# Sheet1.net
KiCad netlist of a schematic drawn in Altium Designer
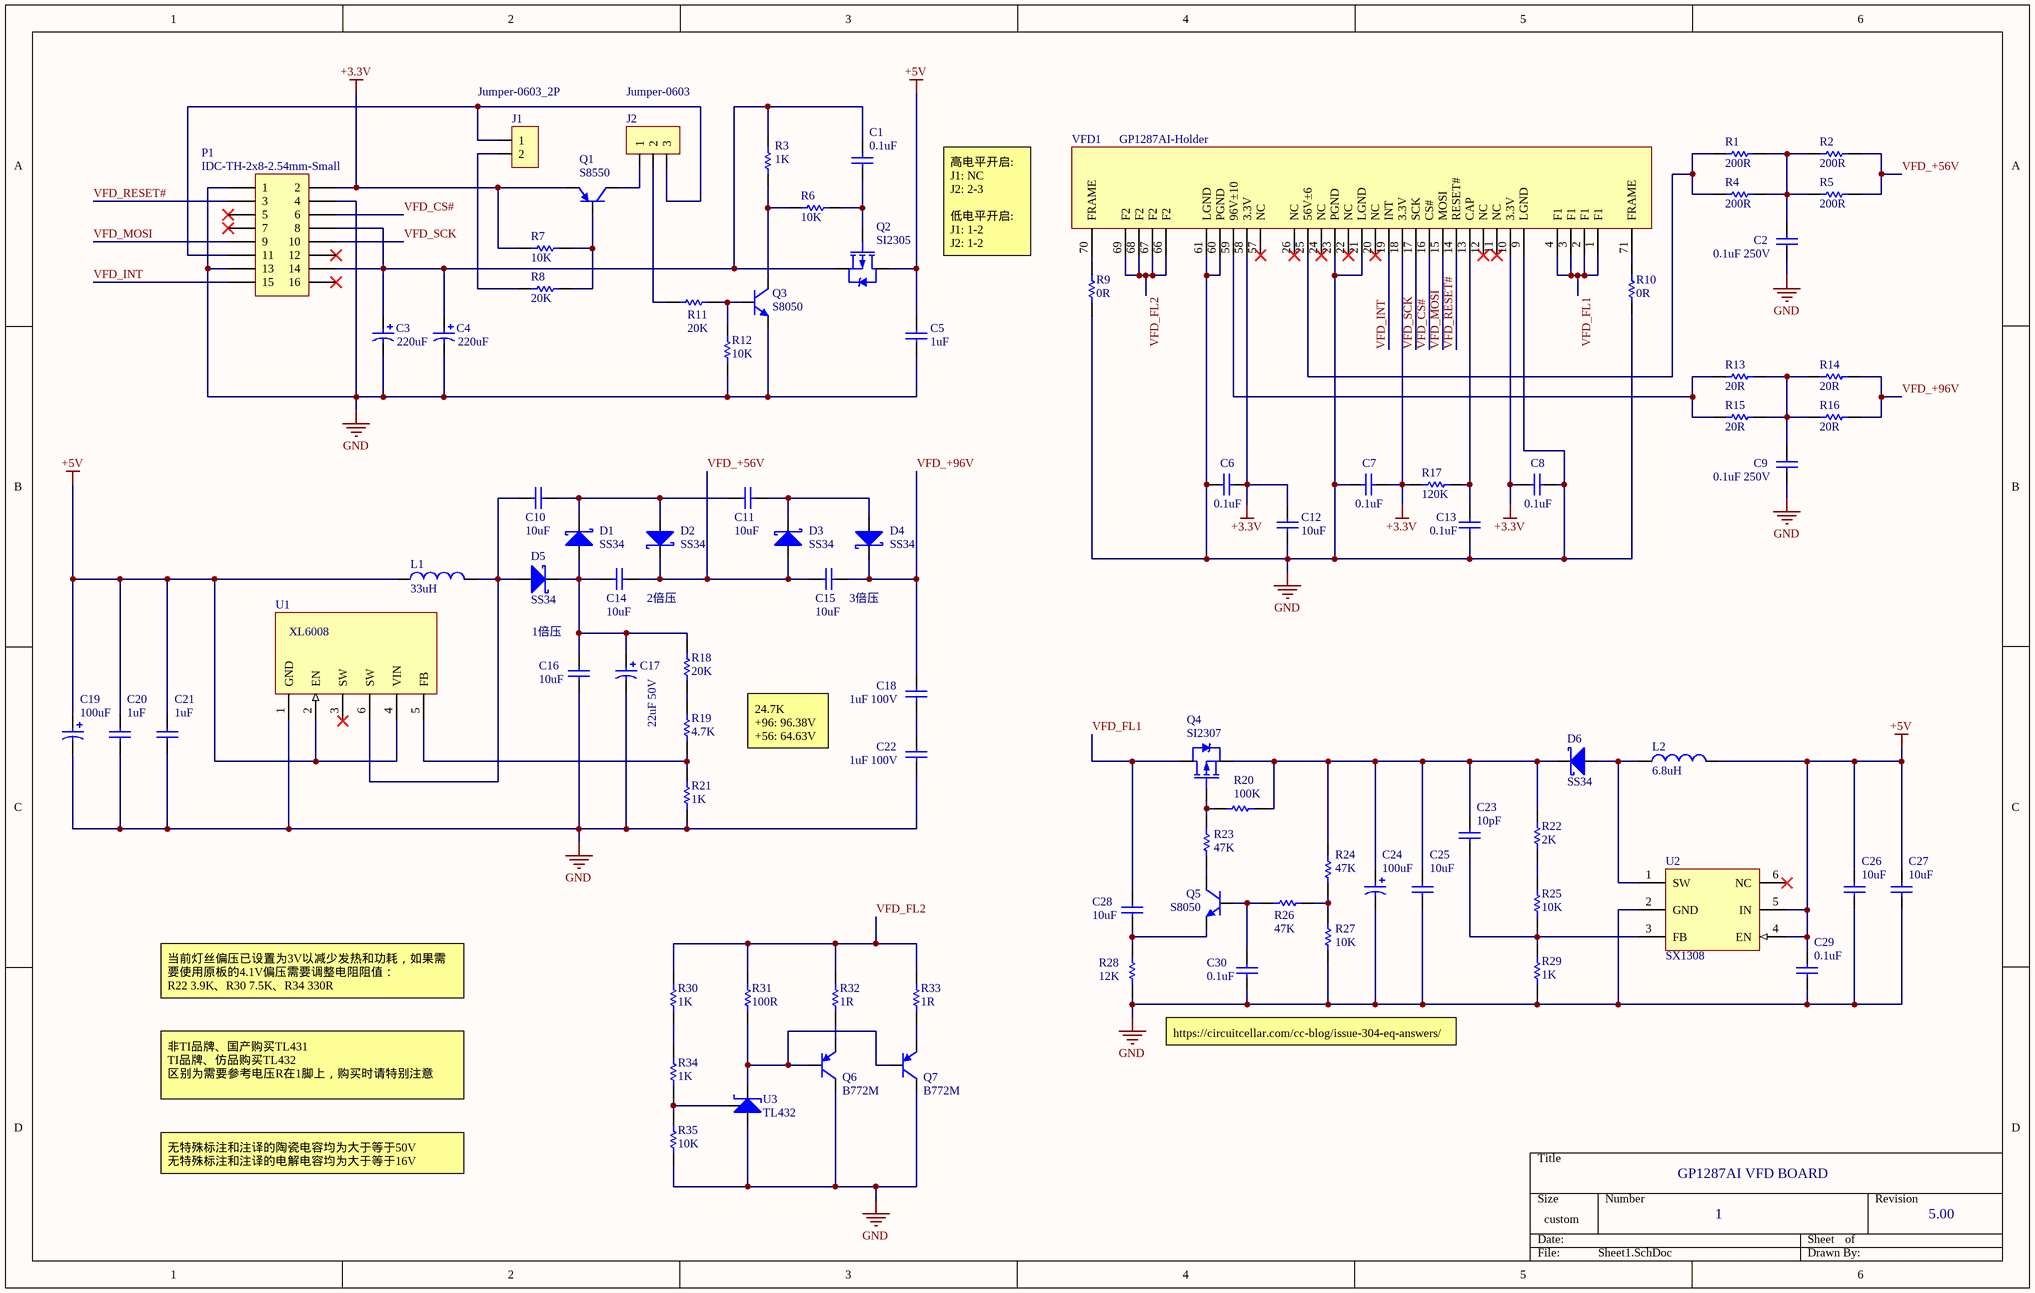
[diagram p0: Sheet1.SchDoc]

(export (version "E")
  (design (tool "Eeschema 10.0.6"))
  (components
    (comp (ref "C1")
      (value "0.1uF")
      (footprint "0603-CAP")
      (libsource (lib "izilzty_Library_Passive") (part "CAP-0603"))
    )
    (comp (ref "C2")
      (value "0.1uF 250V")
      (footprint "1206-CAP")
      (libsource (lib "izilzty_Library_Passive") (part "CAP-1206"))
    )
    (comp (ref "C3")
      (value "220uF")
      (footprint "6.3*7.7-SMD-CAP")
      (libsource (lib "izilzty_Library_Passive") (part "CAP-E-SMD-6.3*7.7"))
    )
    (comp (ref "C4")
      (value "220uF")
      (footprint "6.3*7.7-SMD-CAP")
      (libsource (lib "izilzty_Library_Passive") (part "CAP-E-SMD-6.3*7.7"))
    )
    (comp (ref "C5")
      (value "1uF")
      (footprint "1206-CAP")
      (libsource (lib "izilzty_Library_Passive") (part "CAP-1206"))
    )
    (comp (ref "C6")
      (value "0.1uF")
      (footprint "0603-CAP")
      (libsource (lib "izilzty_Library_Passive") (part "CAP-0603"))
    )
    (comp (ref "C7")
      (value "0.1uF")
      (footprint "0603-CAP")
      (libsource (lib "izilzty_Library_Passive") (part "CAP-0603"))
    )
    (comp (ref "C8")
      (value "0.1uF")
      (footprint "0603-CAP")
      (libsource (lib "izilzty_Library_Passive") (part "CAP-0603"))
    )
    (comp (ref "C9")
      (value "0.1uF 250V")
      (footprint "1206-CAP")
      (libsource (lib "izilzty_Library_Passive") (part "CAP-1206"))
    )
    (comp (ref "C10")
      (value "10uF")
      (footprint "1206-CAP")
      (libsource (lib "izilzty_Library_Passive") (part "CAP-1206"))
    )
    (comp (ref "C11")
      (value "10uF")
      (footprint "1206-CAP")
      (libsource (lib "izilzty_Library_Passive") (part "CAP-1206"))
    )
    (comp (ref "C12")
      (value "10uF")
      (footprint "1206-CAP")
      (libsource (lib "izilzty_Library_Passive") (part "CAP-1206"))
    )
    (comp (ref "C13")
      (value "0.1uF")
      (footprint "0603-CAP")
      (libsource (lib "izilzty_Library_Passive") (part "CAP-0603"))
    )
    (comp (ref "C14")
      (value "10uF")
      (footprint "1206-CAP")
      (libsource (lib "izilzty_Library_Passive") (part "CAP-1206"))
    )
    (comp (ref "C15")
      (value "10uF")
      (footprint "1206-CAP")
      (libsource (lib "izilzty_Library_Passive") (part "CAP-1206"))
    )
    (comp (ref "C16")
      (value "10uF")
      (footprint "1206-CAP")
      (libsource (lib "izilzty_Library_Passive") (part "CAP-1206"))
    )
    (comp (ref "C17")
      (value "22uF 50V")
      (footprint "6.3*5.4-SMD-CAP")
      (libsource (lib "izilzty_Library_Passive") (part "CAP-E-SMD-6.3*5.4"))
    )
    (comp (ref "C18")
      (value "1uF 100V")
      (footprint "1206-CAP")
      (libsource (lib "izilzty_Library_Passive") (part "CAP-1206"))
    )
    (comp (ref "C19")
      (value "100uF")
      (footprint "6.3*5.4-SMD-CAP")
      (libsource (lib "izilzty_Library_Passive") (part "CAP-E-SMD-6.3*5.4"))
    )
    (comp (ref "C20")
      (value "1uF")
      (footprint "0603-CAP")
      (libsource (lib "izilzty_Library_Passive") (part "CAP-0603"))
    )
    (comp (ref "C21")
      (value "1uF")
      (footprint "0603-CAP")
      (libsource (lib "izilzty_Library_Passive") (part "CAP-0603"))
    )
    (comp (ref "C22")
      (value "1uF 100V")
      (footprint "1206-CAP")
      (libsource (lib "izilzty_Library_Passive") (part "CAP-1206"))
    )
    (comp (ref "C23")
      (value "10pF")
      (footprint "0603-CAP")
      (libsource (lib "izilzty_Library_Passive") (part "CAP-0603"))
    )
    (comp (ref "C24")
      (value "100uF")
      (footprint "6.3*5.4-SMD-CAP")
      (libsource (lib "izilzty_Library_Passive") (part "CAP-E-SMD-6.3*5.4"))
    )
    (comp (ref "C25")
      (value "10uF")
      (footprint "1206-CAP")
      (libsource (lib "izilzty_Library_Passive") (part "CAP-1206"))
    )
    (comp (ref "C26")
      (value "10uF")
      (footprint "1206-CAP")
      (libsource (lib "izilzty_Library_Passive") (part "CAP-1206"))
    )
    (comp (ref "C27")
      (value "10uF")
      (footprint "1206-CAP")
      (libsource (lib "izilzty_Library_Passive") (part "CAP-1206"))
    )
    (comp (ref "C28")
      (value "10uF")
      (footprint "1206-CAP")
      (libsource (lib "izilzty_Library_Passive") (part "CAP-1206"))
    )
    (comp (ref "C29")
      (value "0.1uF")
      (footprint "0603-CAP")
      (libsource (lib "izilzty_Library_Passive") (part "CAP-0603"))
    )
    (comp (ref "C30")
      (value "0.1uF")
      (footprint "0603-CAP")
      (libsource (lib "izilzty_Library_Passive") (part "CAP-0603"))
    )
    (comp (ref "D1")
      (value "SS34")
      (footprint "DO-214AC-DIODE-SC_M")
      (libsource (lib "izilzty_Library_Passive") (part "Diode-Schottky-DO214AC"))
    )
    (comp (ref "D2")
      (value "SS34")
      (footprint "DO-214AC-DIODE-SC_M")
      (libsource (lib "izilzty_Library_Passive") (part "Diode-Schottky-DO214AC"))
    )
    (comp (ref "D3")
      (value "SS34")
      (footprint "DO-214AC-DIODE-SC_M")
      (libsource (lib "izilzty_Library_Passive") (part "Diode-Schottky-DO214AC"))
    )
    (comp (ref "D4")
      (value "SS34")
      (footprint "DO-214AC-DIODE-SC_M")
      (libsource (lib "izilzty_Library_Passive") (part "Diode-Schottky-DO214AC"))
    )
    (comp (ref "D5")
      (value "SS34")
      (footprint "DO-214AC-DIODE-SC_M")
      (libsource (lib "izilzty_Library_Passive") (part "Diode-Schottky-DO214AC"))
    )
    (comp (ref "D6")
      (value "SS34")
      (footprint "DO-214AC-DIODE-SC_M")
      (libsource (lib "izilzty_Library_Passive") (part "Diode-Schottky-DO214AC"))
    )
    (comp (ref "J1")
      (value "Jumper-0603_2P")
      (footprint "0603-JUMPER_2P")
      (libsource (lib "izilzty_Library_Passive") (part "Jumper-0603_2P"))
    )
    (comp (ref "J2")
      (value "Jumper-0603")
      (footprint "0603-JUMPER")
      (libsource (lib "izilzty_Library_Passive") (part "Jumper-0603"))
    )
    (comp (ref "L1")
      (value "33uH")
      (footprint "SMD0650_M")
      (libsource (lib "izilzty_Library_Passive") (part "Inductor-SMD0650"))
    )
    (comp (ref "L2")
      (value "6.8uH")
      (footprint "SMD0650_M")
      (libsource (lib "izilzty_Library_Passive") (part "Inductor-SMD0650"))
    )
    (comp (ref "P1")
      (value "IDC-TH-2x8-2.54mm-Small")
      (footprint "IDC_TH_L_SMALL_16P")
      (libsource (lib "izilzty_Library_Connector") (part "IDC-TH-2x8-2.54mm-Small"))
    )
    (comp (ref "Q1")
      (value "S8550")
      (footprint "SOT-23-3_M")
      (libsource (lib "izilzty_Library_Passive") (part "PNP-SOT23-3"))
    )
    (comp (ref "Q2")
      (value "SI2305")
      (footprint "SOT-23-3_M")
      (libsource (lib "izilzty_Library_Passive") (part "PMOS-SOT23-3"))
    )
    (comp (ref "Q3")
      (value "S8050")
      (footprint "SOT-23-3_M")
      (libsource (lib "izilzty_Library_Passive") (part "NPN-SOT23-3"))
    )
    (comp (ref "Q4")
      (value "SI2307")
      (footprint "SOT-23-3_M")
      (libsource (lib "izilzty_Library_Passive") (part "PMOS-SOT23-3"))
    )
    (comp (ref "Q5")
      (value "S8050")
      (footprint "SOT-23-3_M")
      (libsource (lib "izilzty_Library_Passive") (part "NPN-SOT23-3"))
    )
    (comp (ref "Q6")
      (value "B772M")
      (footprint "TO252-2L_M")
      (libsource (lib "izilzty_Library_Passive") (part "PNP-TO252-2L"))
    )
    (comp (ref "Q7")
      (value "B772M")
      (footprint "TO252-2L_M")
      (libsource (lib "izilzty_Library_Passive") (part "PNP-TO252-2L"))
    )
    (comp (ref "R1")
      (value "200R")
      (footprint "1206-RES")
      (libsource (lib "izilzty_Library_Passive") (part "RES-1206"))
    )
    (comp (ref "R2")
      (value "200R")
      (footprint "1206-RES")
      (libsource (lib "izilzty_Library_Passive") (part "RES-1206"))
    )
    (comp (ref "R3")
      (value "1K")
      (footprint "0603-RES")
      (libsource (lib "izilzty_Library_Passive") (part "RES-0603"))
    )
    (comp (ref "R4")
      (value "200R")
      (footprint "1206-RES")
      (libsource (lib "izilzty_Library_Passive") (part "RES-1206"))
    )
    (comp (ref "R5")
      (value "200R")
      (footprint "1206-RES")
      (libsource (lib "izilzty_Library_Passive") (part "RES-1206"))
    )
    (comp (ref "R6")
      (value "10K")
      (footprint "0603-RES")
      (libsource (lib "izilzty_Library_Passive") (part "RES-0603"))
    )
    (comp (ref "R7")
      (value "10K")
      (footprint "0603-RES")
      (libsource (lib "izilzty_Library_Passive") (part "RES-0603"))
    )
    (comp (ref "R8")
      (value "20K")
      (footprint "0603-RES")
      (libsource (lib "izilzty_Library_Passive") (part "RES-0603"))
    )
    (comp (ref "R9")
      (value "0R")
      (footprint "0603-RES")
      (libsource (lib "izilzty_Library_Passive") (part "RES-0603"))
    )
    (comp (ref "R10")
      (value "0R")
      (footprint "0603-RES")
      (libsource (lib "izilzty_Library_Passive") (part "RES-0603"))
    )
    (comp (ref "R11")
      (value "20K")
      (footprint "0603-RES")
      (libsource (lib "izilzty_Library_Passive") (part "RES-0603"))
    )
    (comp (ref "R12")
      (value "10K")
      (footprint "0603-RES")
      (libsource (lib "izilzty_Library_Passive") (part "RES-0603"))
    )
    (comp (ref "R13")
      (value "20R")
      (footprint "1206-RES")
      (libsource (lib "izilzty_Library_Passive") (part "RES-1206"))
    )
    (comp (ref "R14")
      (value "20R")
      (footprint "1206-RES")
      (libsource (lib "izilzty_Library_Passive") (part "RES-1206"))
    )
    (comp (ref "R15")
      (value "20R")
      (footprint "1206-RES")
      (libsource (lib "izilzty_Library_Passive") (part "RES-1206"))
    )
    (comp (ref "R16")
      (value "20R")
      (footprint "1206-RES")
      (libsource (lib "izilzty_Library_Passive") (part "RES-1206"))
    )
    (comp (ref "R17")
      (value "120K")
      (footprint "0603-RES")
      (libsource (lib "izilzty_Library_Passive") (part "RES-0603"))
    )
    (comp (ref "R18")
      (value "20K")
      (footprint "0603-RES")
      (libsource (lib "izilzty_Library_Passive") (part "RES-0603"))
    )
    (comp (ref "R19")
      (value "4.7K")
      (footprint "0603-RES")
      (libsource (lib "izilzty_Library_Passive") (part "RES-0603"))
    )
    (comp (ref "R20")
      (value "100K")
      (footprint "0603-RES")
      (libsource (lib "izilzty_Library_Passive") (part "RES-0603"))
    )
    (comp (ref "R21")
      (value "1K")
      (footprint "0603-RES")
      (libsource (lib "izilzty_Library_Passive") (part "RES-0603"))
    )
    (comp (ref "R22")
      (value "2K")
      (footprint "0603-RES")
      (libsource (lib "izilzty_Library_Passive") (part "RES-0603"))
    )
    (comp (ref "R23")
      (value "47K")
      (footprint "0603-RES")
      (libsource (lib "izilzty_Library_Passive") (part "RES-0603"))
    )
    (comp (ref "R24")
      (value "47K")
      (footprint "0603-RES")
      (libsource (lib "izilzty_Library_Passive") (part "RES-0603"))
    )
    (comp (ref "R25")
      (value "10K")
      (footprint "0603-RES")
      (libsource (lib "izilzty_Library_Passive") (part "RES-0603"))
    )
    (comp (ref "R26")
      (value "47K")
      (footprint "0603-RES")
      (libsource (lib "izilzty_Library_Passive") (part "RES-0603"))
    )
    (comp (ref "R27")
      (value "10K")
      (footprint "0603-RES")
      (libsource (lib "izilzty_Library_Passive") (part "RES-0603"))
    )
    (comp (ref "R28")
      (value "12K")
      (footprint "0603-RES")
      (libsource (lib "izilzty_Library_Passive") (part "RES-0603"))
    )
    (comp (ref "R29")
      (value "1K")
      (footprint "0603-RES")
      (libsource (lib "izilzty_Library_Passive") (part "RES-0603"))
    )
    (comp (ref "R30")
      (value "1K")
      (footprint "0603-RES")
      (libsource (lib "izilzty_Library_Passive") (part "RES-0603"))
    )
    (comp (ref "R31")
      (value "100R")
      (footprint "0603-RES")
      (libsource (lib "izilzty_Library_Passive") (part "RES-0603"))
    )
    (comp (ref "R32")
      (value "1R")
      (footprint "1206-RES")
      (libsource (lib "izilzty_Library_Passive") (part "RES-1206"))
    )
    (comp (ref "R33")
      (value "1R")
      (footprint "1206-RES")
      (libsource (lib "izilzty_Library_Passive") (part "RES-1206"))
    )
    (comp (ref "R34")
      (value "1K")
      (footprint "0603-RES")
      (libsource (lib "izilzty_Library_Passive") (part "RES-0603"))
    )
    (comp (ref "R35")
      (value "10K")
      (footprint "0603-RES")
      (libsource (lib "izilzty_Library_Passive") (part "RES-0603"))
    )
    (comp (ref "U1")
      (value "XL6008")
      (footprint "TO252-5L_M")
      (description "60V 3A  Buck-Boost Converter 400Khz (TO252-5L)")
      (libsource (lib "izilzty_Library_IC") (part "XL6008"))
    )
    (comp (ref "U2")
      (value "SX1308")
      (footprint "SOT-23-6_M")
      (description "26V 2A Boost Converter 1.2MHz (SOT-23-6)")
      (libsource (lib "izilzty_Library_IC") (part "SX1308"))
    )
    (comp (ref "U3")
      (value "TL432")
      (footprint "SOT-23-3_M")
      (description "Precision Programmable Reference")
      (libsource (lib "izilzty_Library_IC") (part "TL432-SOT23-3"))
    )
    (comp (ref "VFD1")
      (value "GP1287AI-Holder")
      (footprint "GP1287AI-HOLDER")
      (description "256*50 Graphic VFD")
      (libsource (lib "izilzty_Library_IC") (part "GP1287AI-Holder"))
    )
  )
  (nets
    (net (code "1") (name "+3.3V") (class "Default")
      (node (ref "C12") (pin "2") (pinfunction "2_2") (pintype "passive"))
      (node (ref "C6") (pin "2") (pinfunction "2_2") (pintype "passive"))
      (node (ref "C7") (pin "2") (pinfunction "2_2") (pintype "passive"))
      (node (ref "C8") (pin "1") (pinfunction "1_1") (pintype "passive"))
      (node (ref "P1") (pin "2") (pinfunction "2_2") (pintype "passive"))
      (node (ref "Q1") (pin "2") (pinfunction "E_2") (pintype "passive"))
      (node (ref "R17") (pin "1") (pinfunction "1_1") (pintype "passive"))
      (node (ref "R7") (pin "1") (pinfunction "1_1") (pintype "passive"))
      (node (ref "VFD1") (pin "10") (pinfunction "3.3V_10") (pintype "passive"))
      (node (ref "VFD1") (pin "18") (pinfunction "3.3V_18") (pintype "passive"))
      (node (ref "VFD1") (pin "58") (pinfunction "3.3V_58") (pintype "passive"))
    )
    (net (code "2") (name "+5V") (class "Default")
      (node (ref "C19") (pin "1") (pinfunction "1_1") (pintype "passive"))
      (node (ref "C20") (pin "2") (pinfunction "2_2") (pintype "passive"))
      (node (ref "C21") (pin "2") (pinfunction "2_2") (pintype "passive"))
      (node (ref "C26") (pin "2") (pinfunction "2_2") (pintype "passive"))
      (node (ref "C27") (pin "2") (pinfunction "2_2") (pintype "passive"))
      (node (ref "C29") (pin "2") (pinfunction "2_2") (pintype "passive"))
      (node (ref "C5") (pin "2") (pinfunction "2_2") (pintype "passive"))
      (node (ref "L1") (pin "1") (pinfunction "1_1") (pintype "passive"))
      (node (ref "L2") (pin "2") (pinfunction "2_2") (pintype "passive"))
      (node (ref "Q2") (pin "3") (pinfunction "D_3") (pintype "passive"))
      (node (ref "U1") (pin "2") (pinfunction "EN_2") (pintype "input"))
      (node (ref "U1") (pin "4") (pinfunction "VIN_4") (pintype "power_in"))
      (node (ref "U2") (pin "4") (pinfunction "EN_4") (pintype "input"))
      (node (ref "U2") (pin "5") (pinfunction "IN_5") (pintype "power_in"))
    )
    (net (code "3") (name "/VFD_+56V") (class "Default")
      (node (ref "C14") (pin "2") (pinfunction "2_2") (pintype "passive"))
      (node (ref "C15") (pin "1") (pinfunction "1_1") (pintype "passive"))
      (node (ref "D2") (pin "1") (pinfunction "K_1") (pintype "passive"))
      (node (ref "D3") (pin "2") (pinfunction "A_2") (pintype "passive"))
      (node (ref "R2") (pin "1") (pinfunction "1_1") (pintype "passive"))
      (node (ref "R5") (pin "1") (pinfunction "1_1") (pintype "passive"))
    )
    (net (code "4") (name "/VFD_+96V") (class "Default")
      (node (ref "C15") (pin "2") (pinfunction "2_2") (pintype "passive"))
      (node (ref "C18") (pin "2") (pinfunction "2_2") (pintype "passive"))
      (node (ref "D4") (pin "1") (pinfunction "K_1") (pintype "passive"))
      (node (ref "R14") (pin "1") (pinfunction "1_1") (pintype "passive"))
      (node (ref "R16") (pin "1") (pinfunction "1_1") (pintype "passive"))
    )
    (net (code "5") (name "/VFD_CS#") (class "Default")
      (node (ref "P1") (pin "6") (pinfunction "6_6") (pintype "passive"))
      (node (ref "VFD1") (pin "16") (pinfunction "CS#_16") (pintype "passive"))
    )
    (net (code "6") (name "/VFD_FL1") (class "Default")
      (node (ref "C28") (pin "2") (pinfunction "2_2") (pintype "passive"))
      (node (ref "Q4") (pin "3") (pinfunction "D_3") (pintype "passive"))
      (node (ref "VFD1") (pin "1") (pinfunction "F1_1") (pintype "power_in"))
      (node (ref "VFD1") (pin "2") (pinfunction "F1_2") (pintype "power_in"))
      (node (ref "VFD1") (pin "3") (pinfunction "F1_3") (pintype "power_in"))
      (node (ref "VFD1") (pin "4") (pinfunction "F1_4") (pintype "power_in"))
    )
    (net (code "7") (name "/VFD_FL2") (class "Default")
      (node (ref "R30") (pin "2") (pinfunction "2_2") (pintype "passive"))
      (node (ref "R31") (pin "2") (pinfunction "2_2") (pintype "passive"))
      (node (ref "R32") (pin "2") (pinfunction "2_2") (pintype "passive"))
      (node (ref "R33") (pin "2") (pinfunction "2_2") (pintype "passive"))
      (node (ref "VFD1") (pin "66") (pinfunction "F2_66") (pintype "passive"))
      (node (ref "VFD1") (pin "67") (pinfunction "F2_67") (pintype "passive"))
      (node (ref "VFD1") (pin "68") (pinfunction "F2_68") (pintype "passive"))
      (node (ref "VFD1") (pin "69") (pinfunction "F2_69") (pintype "passive"))
    )
    (net (code "8") (name "/VFD_INT") (class "Default")
      (node (ref "P1") (pin "15") (pinfunction "15_15") (pintype "passive"))
      (node (ref "VFD1") (pin "19") (pinfunction "INT_19") (pintype "passive"))
    )
    (net (code "9") (name "/VFD_MOSI") (class "Default")
      (node (ref "P1") (pin "9") (pinfunction "9_9") (pintype "passive"))
      (node (ref "VFD1") (pin "15") (pinfunction "MOSI_15") (pintype "passive"))
    )
    (net (code "10") (name "/VFD_RESET#") (class "Default")
      (node (ref "P1") (pin "3") (pinfunction "3_3") (pintype "passive"))
      (node (ref "VFD1") (pin "14") (pinfunction "RESET#_14") (pintype "passive"))
    )
    (net (code "11") (name "/VFD_SCK") (class "Default")
      (node (ref "P1") (pin "10") (pinfunction "10_10") (pintype "passive"))
      (node (ref "VFD1") (pin "17") (pinfunction "SCK_17") (pintype "passive"))
    )
    (net (code "12") (name "GND") (class "Default")
      (node (ref "C12") (pin "1") (pinfunction "1_1") (pintype "passive"))
      (node (ref "C13") (pin "1") (pinfunction "1_1") (pintype "passive"))
      (node (ref "C16") (pin "1") (pinfunction "1_1") (pintype "passive"))
      (node (ref "C17") (pin "2") (pinfunction "2_2") (pintype "passive"))
      (node (ref "C19") (pin "2") (pinfunction "2_2") (pintype "passive"))
      (node (ref "C2") (pin "1") (pinfunction "1_1") (pintype "passive"))
      (node (ref "C20") (pin "1") (pinfunction "1_1") (pintype "passive"))
      (node (ref "C21") (pin "1") (pinfunction "1_1") (pintype "passive"))
      (node (ref "C22") (pin "1") (pinfunction "1_1") (pintype "passive"))
      (node (ref "C24") (pin "2") (pinfunction "2_2") (pintype "passive"))
      (node (ref "C25") (pin "1") (pinfunction "1_1") (pintype "passive"))
      (node (ref "C26") (pin "1") (pinfunction "1_1") (pintype "passive"))
      (node (ref "C27") (pin "1") (pinfunction "1_1") (pintype "passive"))
      (node (ref "C29") (pin "1") (pinfunction "1_1") (pintype "passive"))
      (node (ref "C3") (pin "2") (pinfunction "2_2") (pintype "passive"))
      (node (ref "C30") (pin "1") (pinfunction "1_1") (pintype "passive"))
      (node (ref "C4") (pin "2") (pinfunction "2_2") (pintype "passive"))
      (node (ref "C5") (pin "1") (pinfunction "1_1") (pintype "passive"))
      (node (ref "C6") (pin "1") (pinfunction "1_1") (pintype "passive"))
      (node (ref "C7") (pin "1") (pinfunction "1_1") (pintype "passive"))
      (node (ref "C8") (pin "2") (pinfunction "2_2") (pintype "passive"))
      (node (ref "C9") (pin "1") (pinfunction "1_1") (pintype "passive"))
      (node (ref "P1") (pin "1") (pinfunction "1_1") (pintype "passive"))
      (node (ref "P1") (pin "13") (pinfunction "13_13") (pintype "passive"))
      (node (ref "P1") (pin "4") (pinfunction "4_4") (pintype "passive"))
      (node (ref "Q3") (pin "2") (pinfunction "E_2") (pintype "passive"))
      (node (ref "Q6") (pin "2") (pinfunction "C_2") (pintype "passive"))
      (node (ref "Q7") (pin "2") (pinfunction "C_2") (pintype "passive"))
      (node (ref "R10") (pin "2") (pinfunction "2_2") (pintype "passive"))
      (node (ref "R12") (pin "2") (pinfunction "2_2") (pintype "passive"))
      (node (ref "R21") (pin "2") (pinfunction "2_2") (pintype "passive"))
      (node (ref "R27") (pin "1") (pinfunction "1_1") (pintype "passive"))
      (node (ref "R28") (pin "1") (pinfunction "1_1") (pintype "passive"))
      (node (ref "R29") (pin "1") (pinfunction "1_1") (pintype "passive"))
      (node (ref "R35") (pin "1") (pinfunction "1_1") (pintype "passive"))
      (node (ref "R9") (pin "2") (pinfunction "2_2") (pintype "passive"))
      (node (ref "U1") (pin "1") (pinfunction "GND_1") (pintype "power_in"))
      (node (ref "U2") (pin "2") (pinfunction "GND_2") (pintype "power_in"))
      (node (ref "U3") (pin "3") (pinfunction "A_3") (pintype "passive"))
      (node (ref "VFD1") (pin "21") (pinfunction "LGND_21") (pintype "passive"))
      (node (ref "VFD1") (pin "23") (pinfunction "PGND_23") (pintype "passive"))
      (node (ref "VFD1") (pin "60") (pinfunction "PGND_60") (pintype "passive"))
      (node (ref "VFD1") (pin "61") (pinfunction "LGND_61") (pintype "passive"))
      (node (ref "VFD1") (pin "9") (pinfunction "LGND_9") (pintype "passive"))
    )
    (net (code "13") (name "Net-(C2-Pad2)") (class "Default")
      (node (ref "C2") (pin "2") (pinfunction "2_2") (pintype "passive"))
      (node (ref "R1") (pin "1") (pinfunction "1_1") (pintype "passive"))
      (node (ref "R2") (pin "2") (pinfunction "2_2") (pintype "passive"))
      (node (ref "R4") (pin "1") (pinfunction "1_1") (pintype "passive"))
      (node (ref "R5") (pin "2") (pinfunction "2_2") (pintype "passive"))
    )
    (net (code "14") (name "Net-(C9-Pad2)") (class "Default")
      (node (ref "C9") (pin "2") (pinfunction "2_2") (pintype "passive"))
      (node (ref "R13") (pin "1") (pinfunction "1_1") (pintype "passive"))
      (node (ref "R14") (pin "2") (pinfunction "2_2") (pintype "passive"))
      (node (ref "R15") (pin "1") (pinfunction "1_1") (pintype "passive"))
      (node (ref "R16") (pin "2") (pinfunction "2_2") (pintype "passive"))
    )
    (net (code "15") (name "Net-(C18-Pad1)") (class "Default")
      (node (ref "C18") (pin "1") (pinfunction "1_1") (pintype "passive"))
      (node (ref "C22") (pin "2") (pinfunction "2_2") (pintype "passive"))
    )
    (net (code "16") (name "Net-(D1-A)") (class "Default")
      (node (ref "C14") (pin "1") (pinfunction "1_1") (pintype "passive"))
      (node (ref "C16") (pin "2") (pinfunction "2_2") (pintype "passive"))
      (node (ref "C17") (pin "1") (pinfunction "1_1") (pintype "passive"))
      (node (ref "D1") (pin "2") (pinfunction "A_2") (pintype "passive"))
      (node (ref "D5") (pin "1") (pinfunction "K_1") (pintype "passive"))
      (node (ref "R18") (pin "1") (pinfunction "1_1") (pintype "passive"))
    )
    (net (code "17") (name "Net-(D1-K)") (class "Default")
      (node (ref "C10") (pin "2") (pinfunction "2_2") (pintype "passive"))
      (node (ref "C11") (pin "1") (pinfunction "1_1") (pintype "passive"))
      (node (ref "D1") (pin "1") (pinfunction "K_1") (pintype "passive"))
      (node (ref "D2") (pin "2") (pinfunction "A_2") (pintype "passive"))
    )
    (net (code "18") (name "Net-(D3-K)") (class "Default")
      (node (ref "C11") (pin "2") (pinfunction "2_2") (pintype "passive"))
      (node (ref "D3") (pin "1") (pinfunction "K_1") (pintype "passive"))
      (node (ref "D4") (pin "2") (pinfunction "A_2") (pintype "passive"))
    )
    (net (code "19") (name "Net-(D5-A)") (class "Default")
      (node (ref "C10") (pin "1") (pinfunction "1_1") (pintype "passive"))
      (node (ref "D5") (pin "2") (pinfunction "A_2") (pintype "passive"))
      (node (ref "L1") (pin "2") (pinfunction "2_2") (pintype "passive"))
      (node (ref "U1") (pin "6") (pinfunction "SW_6") (pintype "power_in"))
    )
    (net (code "20") (name "Net-(D6-A)") (class "Default")
      (node (ref "D6") (pin "2") (pinfunction "A_2") (pintype "passive"))
      (node (ref "L2") (pin "1") (pinfunction "1_1") (pintype "passive"))
      (node (ref "U2") (pin "1") (pinfunction "SW_1") (pintype "passive"))
    )
    (net (code "21") (name "Net-(D6-K)") (class "Default")
      (node (ref "C23") (pin "2") (pinfunction "2_2") (pintype "passive"))
      (node (ref "C24") (pin "1") (pinfunction "1_1") (pintype "passive"))
      (node (ref "C25") (pin "2") (pinfunction "2_2") (pintype "passive"))
      (node (ref "D6") (pin "1") (pinfunction "K_1") (pintype "passive"))
      (node (ref "Q4") (pin "2") (pinfunction "S_2") (pintype "passive"))
      (node (ref "R20") (pin "2") (pinfunction "2_2") (pintype "passive"))
      (node (ref "R22") (pin "2") (pinfunction "2_2") (pintype "passive"))
      (node (ref "R24") (pin "2") (pinfunction "2_2") (pintype "passive"))
    )
    (net (code "22") (name "Net-(J1-Pad1)") (class "Default")
      (node (ref "J1") (pin "1") (pinfunction "1_1") (pintype "passive"))
      (node (ref "J2") (pin "3") (pinfunction "3_3") (pintype "passive"))
      (node (ref "P1") (pin "11") (pinfunction "11_11") (pintype "passive"))
    )
    (net (code "23") (name "Net-(J1-Pad2)") (class "Default")
      (node (ref "J1") (pin "2") (pinfunction "2_2") (pintype "passive"))
      (node (ref "R8") (pin "1") (pinfunction "1_1") (pintype "passive"))
    )
    (net (code "24") (name "Net-(J2-Pad2)") (class "Default")
      (node (ref "J2") (pin "2") (pinfunction "2_2") (pintype "passive"))
      (node (ref "R11") (pin "1") (pinfunction "1_1") (pintype "passive"))
    )
    (net (code "25") (name "Net-(Q1-B)") (class "Default")
      (node (ref "Q1") (pin "1") (pinfunction "B_1") (pintype "passive"))
      (node (ref "R7") (pin "2") (pinfunction "2_2") (pintype "passive"))
      (node (ref "R8") (pin "2") (pinfunction "2_2") (pintype "passive"))
    )
    (net (code "26") (name "Net-(Q1-C)") (class "Default")
      (node (ref "J2") (pin "1") (pinfunction "1_1") (pintype "passive"))
      (node (ref "Q1") (pin "3") (pinfunction "C_3") (pintype "passive"))
    )
    (net (code "27") (name "Net-(Q2-G)") (class "Default")
      (node (ref "C1") (pin "1") (pinfunction "1_1") (pintype "passive"))
      (node (ref "Q2") (pin "1") (pinfunction "G_1") (pintype "passive"))
      (node (ref "R6") (pin "1") (pinfunction "1_1") (pintype "passive"))
    )
    (net (code "28") (name "Net-(Q2-S)") (class "Default")
      (node (ref "C1") (pin "2") (pinfunction "2_2") (pintype "passive"))
      (node (ref "C3") (pin "1") (pinfunction "1_1") (pintype "passive"))
      (node (ref "C4") (pin "1") (pinfunction "1_1") (pintype "passive"))
      (node (ref "P1") (pin "14") (pinfunction "14_14") (pintype "passive"))
      (node (ref "P1") (pin "8") (pinfunction "8_8") (pintype "passive"))
      (node (ref "Q2") (pin "2") (pinfunction "S_2") (pintype "passive"))
      (node (ref "R3") (pin "2") (pinfunction "2_2") (pintype "passive"))
    )
    (net (code "29") (name "Net-(Q3-B)") (class "Default")
      (node (ref "Q3") (pin "1") (pinfunction "B_1") (pintype "passive"))
      (node (ref "R11") (pin "2") (pinfunction "2_2") (pintype "passive"))
      (node (ref "R12") (pin "1") (pinfunction "1_1") (pintype "passive"))
    )
    (net (code "30") (name "Net-(Q3-C)") (class "Default")
      (node (ref "Q3") (pin "3") (pinfunction "C_3") (pintype "passive"))
      (node (ref "R3") (pin "1") (pinfunction "1_1") (pintype "passive"))
      (node (ref "R6") (pin "2") (pinfunction "2_2") (pintype "passive"))
    )
    (net (code "31") (name "Net-(Q4-G)") (class "Default")
      (node (ref "Q4") (pin "1") (pinfunction "G_1") (pintype "passive"))
      (node (ref "R20") (pin "1") (pinfunction "1_1") (pintype "passive"))
      (node (ref "R23") (pin "2") (pinfunction "2_2") (pintype "passive"))
    )
    (net (code "32") (name "Net-(Q5-B)") (class "Default")
      (node (ref "C30") (pin "2") (pinfunction "2_2") (pintype "passive"))
      (node (ref "Q5") (pin "1") (pinfunction "B_1") (pintype "passive"))
      (node (ref "R26") (pin "1") (pinfunction "1_1") (pintype "passive"))
    )
    (net (code "33") (name "Net-(Q5-C)") (class "Default")
      (node (ref "Q5") (pin "3") (pinfunction "C_3") (pintype "passive"))
      (node (ref "R23") (pin "1") (pinfunction "1_1") (pintype "passive"))
    )
    (net (code "34") (name "Net-(Q5-E)") (class "Default")
      (node (ref "C28") (pin "1") (pinfunction "1_1") (pintype "passive"))
      (node (ref "Q5") (pin "2") (pinfunction "E_2") (pintype "passive"))
      (node (ref "R28") (pin "2") (pinfunction "2_2") (pintype "passive"))
    )
    (net (code "35") (name "Net-(Q6-B)") (class "Default")
      (node (ref "Q6") (pin "1") (pinfunction "B_1") (pintype "passive"))
      (node (ref "Q7") (pin "1") (pinfunction "B_1") (pintype "passive"))
      (node (ref "R31") (pin "1") (pinfunction "1_1") (pintype "passive"))
      (node (ref "U3") (pin "2") (pinfunction "K_2") (pintype "passive"))
    )
    (net (code "36") (name "Net-(Q6-E)") (class "Default")
      (node (ref "Q6") (pin "3") (pinfunction "E_3") (pintype "passive"))
      (node (ref "R32") (pin "1") (pinfunction "1_1") (pintype "passive"))
    )
    (net (code "37") (name "Net-(Q7-E)") (class "Default")
      (node (ref "Q7") (pin "3") (pinfunction "E_3") (pintype "passive"))
      (node (ref "R33") (pin "1") (pinfunction "1_1") (pintype "passive"))
    )
    (net (code "38") (name "Net-(R9-Pad1)") (class "Default")
      (node (ref "R9") (pin "1") (pinfunction "1_1") (pintype "passive"))
      (node (ref "VFD1") (pin "70") (pinfunction "FRAME_70") (pintype "passive"))
    )
    (net (code "39") (name "Net-(R10-Pad1)") (class "Default")
      (node (ref "R10") (pin "1") (pinfunction "1_1") (pintype "passive"))
      (node (ref "VFD1") (pin "71") (pinfunction "FRAME_71") (pintype "passive"))
    )
    (net (code "40") (name "Net-(R18-Pad2)") (class "Default")
      (node (ref "R18") (pin "2") (pinfunction "2_2") (pintype "passive"))
      (node (ref "R19") (pin "1") (pinfunction "1_1") (pintype "passive"))
    )
    (net (code "41") (name "Net-(R22-Pad1)") (class "Default")
      (node (ref "R22") (pin "1") (pinfunction "1_1") (pintype "passive"))
      (node (ref "R25") (pin "2") (pinfunction "2_2") (pintype "passive"))
    )
    (net (code "42") (name "Net-(R24-Pad1)") (class "Default")
      (node (ref "R24") (pin "1") (pinfunction "1_1") (pintype "passive"))
      (node (ref "R26") (pin "2") (pinfunction "2_2") (pintype "passive"))
      (node (ref "R27") (pin "2") (pinfunction "2_2") (pintype "passive"))
    )
    (net (code "43") (name "Net-(R30-Pad1)") (class "Default")
      (node (ref "R30") (pin "1") (pinfunction "1_1") (pintype "passive"))
      (node (ref "R34") (pin "2") (pinfunction "2_2") (pintype "passive"))
    )
    (net (code "44") (name "Net-(U1-FB)") (class "Default")
      (node (ref "R19") (pin "2") (pinfunction "2_2") (pintype "passive"))
      (node (ref "R21") (pin "1") (pinfunction "1_1") (pintype "passive"))
      (node (ref "U1") (pin "5") (pinfunction "FB_5") (pintype "passive"))
    )
    (net (code "45") (name "Net-(U2-FB)") (class "Default")
      (node (ref "C23") (pin "1") (pinfunction "1_1") (pintype "passive"))
      (node (ref "R25") (pin "1") (pinfunction "1_1") (pintype "passive"))
      (node (ref "R29") (pin "2") (pinfunction "2_2") (pintype "passive"))
      (node (ref "U2") (pin "3") (pinfunction "FB_3") (pintype "passive"))
    )
    (net (code "46") (name "Net-(U3-R)") (class "Default")
      (node (ref "R34") (pin "1") (pinfunction "1_1") (pintype "passive"))
      (node (ref "R35") (pin "2") (pinfunction "2_2") (pintype "passive"))
      (node (ref "U3") (pin "1") (pinfunction "R_1") (pintype "passive"))
    )
    (net (code "47") (name "Net-(VFD1-56V±6)") (class "Default")
      (node (ref "R1") (pin "2") (pinfunction "2_2") (pintype "passive"))
      (node (ref "R4") (pin "2") (pinfunction "2_2") (pintype "passive"))
      (node (ref "VFD1") (pin "25") (pinfunction "56V±6_25") (pintype "passive"))
    )
    (net (code "48") (name "Net-(VFD1-96V±10)") (class "Default")
      (node (ref "R13") (pin "2") (pinfunction "2_2") (pintype "passive"))
      (node (ref "R15") (pin "2") (pinfunction "2_2") (pintype "passive"))
      (node (ref "VFD1") (pin "59") (pinfunction "96V±10_59") (pintype "passive"))
    )
    (net (code "49") (name "Net-(VFD1-CAP)") (class "Default")
      (node (ref "C13") (pin "2") (pinfunction "2_2") (pintype "passive"))
      (node (ref "R17") (pin "2") (pinfunction "2_2") (pintype "passive"))
      (node (ref "VFD1") (pin "13") (pinfunction "CAP_13") (pintype "passive"))
    )
    (net (code "50") (name "unconnected-(P1-Pad5)") (class "Default")
      (node (ref "P1") (pin "5") (pinfunction "5_5") (pintype "passive+no_connect"))
    )
    (net (code "51") (name "unconnected-(P1-Pad7)") (class "Default")
      (node (ref "P1") (pin "7") (pinfunction "7_7") (pintype "passive+no_connect"))
    )
    (net (code "52") (name "unconnected-(P1-Pad12)") (class "Default")
      (node (ref "P1") (pin "12") (pinfunction "12_12") (pintype "passive+no_connect"))
    )
    (net (code "53") (name "unconnected-(P1-Pad16)") (class "Default")
      (node (ref "P1") (pin "16") (pinfunction "16_16") (pintype "passive+no_connect"))
    )
    (net (code "54") (name "unconnected-(U1-SW-Pad3)") (class "Default")
      (node (ref "U1") (pin "3") (pinfunction "SW_3") (pintype "power_in+no_connect"))
    )
    (net (code "55") (name "unconnected-(U2-NC-Pad6)") (class "Default")
      (node (ref "U2") (pin "6") (pinfunction "NC_6") (pintype "passive+no_connect"))
    )
    (net (code "56") (name "unconnected-(VFD1-NC-Pad11)") (class "Default")
      (node (ref "VFD1") (pin "11") (pinfunction "NC_11") (pintype "passive+no_connect"))
    )
    (net (code "57") (name "unconnected-(VFD1-NC-Pad12)") (class "Default")
      (node (ref "VFD1") (pin "12") (pinfunction "NC_12") (pintype "passive+no_connect"))
    )
    (net (code "58") (name "unconnected-(VFD1-NC-Pad20)") (class "Default")
      (node (ref "VFD1") (pin "20") (pinfunction "NC_20") (pintype "passive+no_connect"))
    )
    (net (code "59") (name "unconnected-(VFD1-NC-Pad22)") (class "Default")
      (node (ref "VFD1") (pin "22") (pinfunction "NC_22") (pintype "passive+no_connect"))
    )
    (net (code "60") (name "unconnected-(VFD1-NC-Pad24)") (class "Default")
      (node (ref "VFD1") (pin "24") (pinfunction "NC_24") (pintype "passive+no_connect"))
    )
    (net (code "61") (name "unconnected-(VFD1-NC-Pad26)") (class "Default")
      (node (ref "VFD1") (pin "26") (pinfunction "NC_26") (pintype "passive+no_connect"))
    )
    (net (code "62") (name "unconnected-(VFD1-NC-Pad57)") (class "Default")
      (node (ref "VFD1") (pin "57") (pinfunction "NC_57") (pintype "passive+no_connect"))
    )
  )
)
